# jtag.net
KiCad netlist of a schematic drawn in Altium Designer
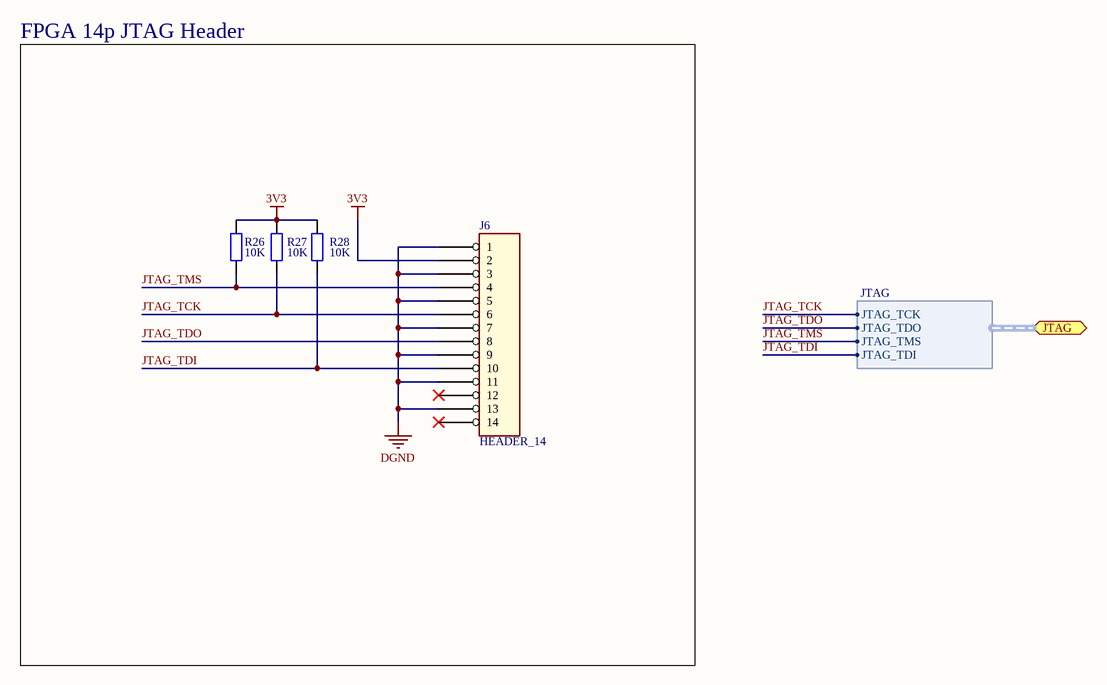
[diagram p0: jtag.SchDoc]

(export (version "E")
  (design (tool "Eeschema 10.0.6"))
  (components
    (comp (ref "J6")
      (value "HEADER_14")
      (footprint "Male Box Header 2mm 14P")
      (description "Male Box Header 14 poles")
      (fields (field (name "MANUFACTURER") "Würth"))
      (libsource (lib "Database_heig-vd") (part "HEADER_14"))
    )
    (comp (ref "R26")
      (value "10K")
      (footprint "SM/R_0603")
      (description "Résistance 0603 63mW 1% 10K")
      (fields (field (name "MANUFACTURER") "Multicomp") (field (name "POWER") "63mW"))
      (libsource (lib "Database_heig-vd") (part "Res"))
    )
    (comp (ref "R27")
      (value "10K")
      (footprint "SM/R_0603")
      (description "Résistance 0603 63mW 1% 10K")
      (fields (field (name "MANUFACTURER") "Multicomp") (field (name "POWER") "63mW"))
      (libsource (lib "Database_heig-vd") (part "Res"))
    )
    (comp (ref "R28")
      (value "10K")
      (footprint "SM/R_0603")
      (description "Résistance 0603 63mW 1% 10K")
      (fields (field (name "MANUFACTURER") "Multicomp") (field (name "POWER") "63mW"))
      (libsource (lib "Database_heig-vd") (part "Res"))
    )
  )
  (nets
    (net (code "2") (name "/JTAG_TCK") (class "Default")
      (node (ref "J6") (pin "6") (pinfunction "6_6") (pintype "passive"))
      (node (ref "R27") (pin "2") (pinfunction "2_2") (pintype "passive"))
    )
    (net (code "3") (name "/JTAG_TDI") (class "Default")
      (node (ref "J6") (pin "10") (pinfunction "10_10") (pintype "passive"))
      (node (ref "R28") (pin "2") (pinfunction "2_2") (pintype "passive"))
    )
    (net (code "4") (name "/JTAG_TDO") (class "Default")
      (node (ref "J6") (pin "8") (pinfunction "8_8") (pintype "passive"))
    )
    (net (code "5") (name "/JTAG_TMS") (class "Default")
      (node (ref "J6") (pin "4") (pinfunction "4_4") (pintype "passive"))
      (node (ref "R26") (pin "2") (pinfunction "2_2") (pintype "passive"))
    )
    (net (code "7") (name "3V3") (class "Default")
      (node (ref "J6") (pin "2") (pinfunction "2_2") (pintype "passive"))
      (node (ref "R26") (pin "1") (pinfunction "1_1") (pintype "passive"))
      (node (ref "R27") (pin "1") (pinfunction "1_1") (pintype "passive"))
      (node (ref "R28") (pin "1") (pinfunction "1_1") (pintype "passive"))
    )
    (net (code "8") (name "DGND") (class "Default")
      (node (ref "J6") (pin "1") (pinfunction "1_1") (pintype "passive"))
      (node (ref "J6") (pin "11") (pinfunction "11_11") (pintype "passive"))
      (node (ref "J6") (pin "13") (pinfunction "13_13") (pintype "passive"))
      (node (ref "J6") (pin "3") (pinfunction "3_3") (pintype "passive"))
      (node (ref "J6") (pin "5") (pinfunction "5_5") (pintype "passive"))
      (node (ref "J6") (pin "7") (pinfunction "7_7") (pintype "passive"))
      (node (ref "J6") (pin "9") (pinfunction "9_9") (pintype "passive"))
    )
    (net (code "9") (name "unconnected-(J6-Pad12)") (class "Default")
      (node (ref "J6") (pin "12") (pinfunction "12_12") (pintype "passive+no_connect"))
    )
    (net (code "10") (name "unconnected-(J6-Pad14)") (class "Default")
      (node (ref "J6") (pin "14") (pinfunction "14_14") (pintype "passive+no_connect"))
    )
  )
)
